# analog-out-and-pwr-amp.net
KiCad netlist of a schematic drawn in EAGLE
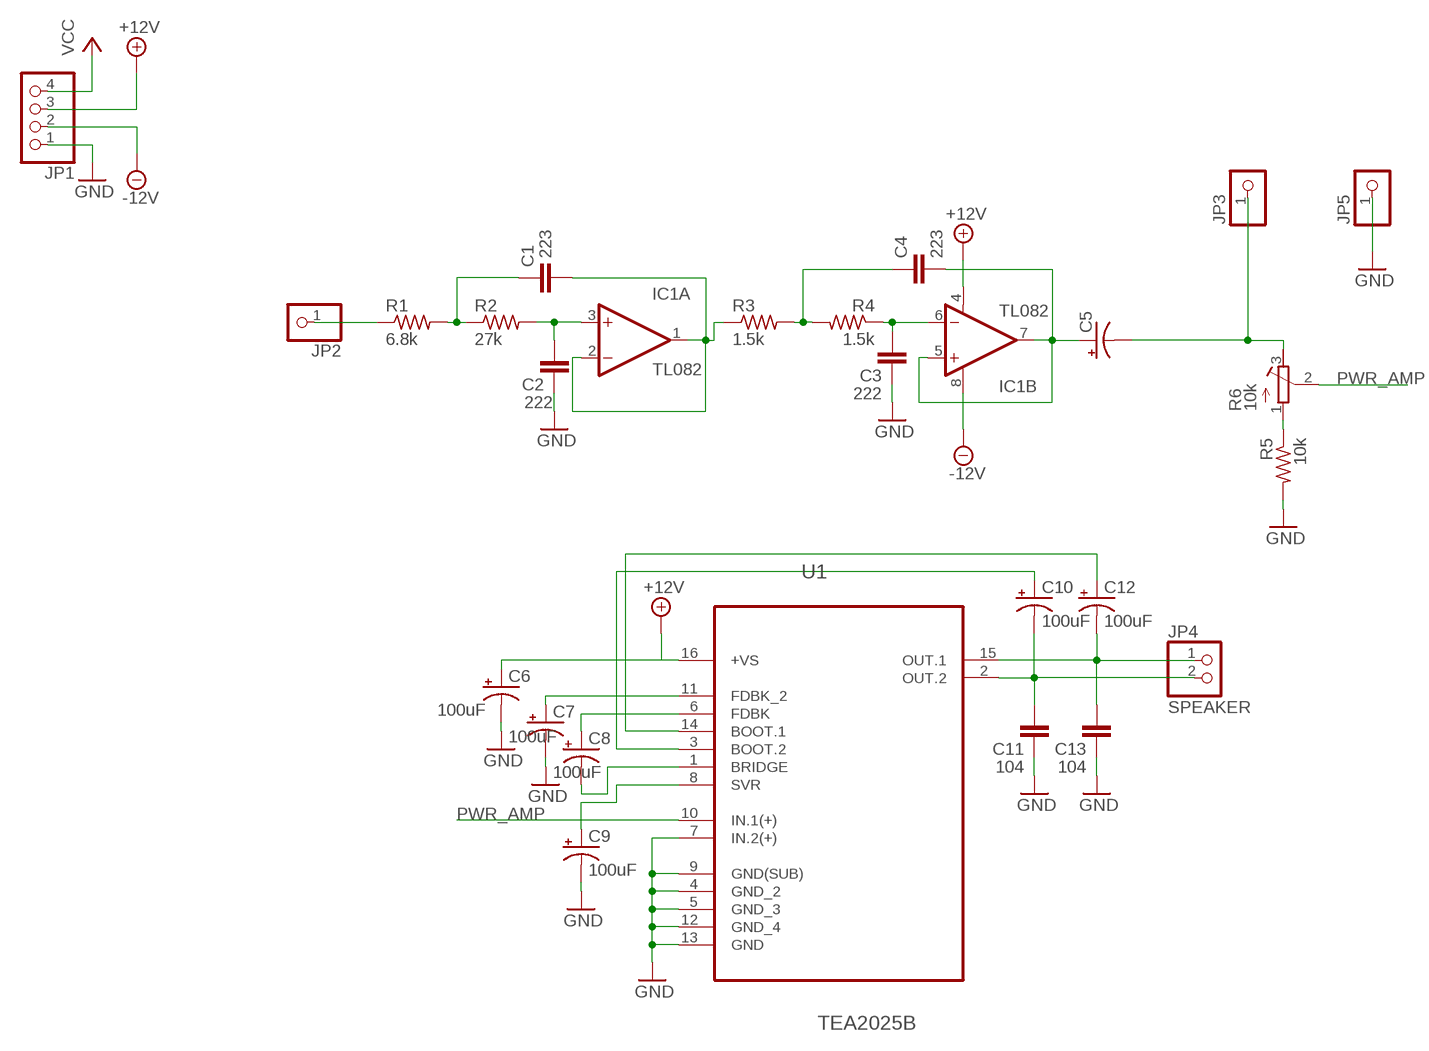
[diagram p0: schematic, sheet 1]

(export (version "E")
  (design (tool "Eeschema 10.0.6"))
  (components
    (comp (ref "C1")
      (value "223")
      (footprint "eagle-import:C025-060X050")
      (libsource (lib "eagle-import") (part "C-EUCERAMIC-CAP-COMMON"))
    )
    (comp (ref "C2")
      (value "222")
      (footprint "eagle-import:C025-060X050")
      (libsource (lib "eagle-import") (part "C-EUCERAMIC-CAP-COMMON"))
    )
    (comp (ref "C3")
      (value "222")
      (footprint "eagle-import:C025-060X050")
      (libsource (lib "eagle-import") (part "C-EUCERAMIC-CAP-COMMON"))
    )
    (comp (ref "C4")
      (value "223")
      (footprint "eagle-import:C025-060X050")
      (libsource (lib "eagle-import") (part "C-EUCERAMIC-CAP-COMMON"))
    )
    (comp (ref "C5")
      (value "CPOL-USSANYO_D")
      (footprint "eagle-import:POL-CAP-COMMON")
      (libsource (lib "eagle-import") (part "CPOL-USSANYO_D"))
    )
    (comp (ref "C6")
      (value "100uF")
      (footprint "eagle-import:POL-CAP-COMMON")
      (libsource (lib "eagle-import") (part "CPOL-USSANYO_D"))
    )
    (comp (ref "C7")
      (value "100uF")
      (footprint "eagle-import:POL-CAP-COMMON")
      (libsource (lib "eagle-import") (part "CPOL-USSANYO_D"))
    )
    (comp (ref "C8")
      (value "100uF")
      (footprint "eagle-import:POL-CAP-COMMON")
      (libsource (lib "eagle-import") (part "CPOL-USSANYO_D"))
    )
    (comp (ref "C9")
      (value "100uF")
      (footprint "eagle-import:POL-CAP-COMMON")
      (libsource (lib "eagle-import") (part "CPOL-USSANYO_D"))
    )
    (comp (ref "C10")
      (value "100uF")
      (footprint "eagle-import:POL-CAP-COMMON")
      (libsource (lib "eagle-import") (part "CPOL-USSANYO_D"))
    )
    (comp (ref "C11")
      (value "104")
      (footprint "eagle-import:C025-060X050")
      (libsource (lib "eagle-import") (part "C-EUCERAMIC-CAP-COMMON"))
    )
    (comp (ref "C12")
      (value "100uF")
      (footprint "eagle-import:POL-CAP-COMMON")
      (libsource (lib "eagle-import") (part "CPOL-USSANYO_D"))
    )
    (comp (ref "C13")
      (value "104")
      (footprint "eagle-import:C025-060X050")
      (libsource (lib "eagle-import") (part "C-EUCERAMIC-CAP-COMMON"))
    )
    (comp (ref "IC1")
      (value "TL082")
      (footprint "eagle-import:DIP08")
      (libsource (lib "eagle-import") (part "TL082"))
    )
    (comp (ref "JP1")
      (value "PINHD-1X4")
      (footprint "eagle-import:1X04")
      (libsource (lib "eagle-import") (part "PINHD-1X4"))
    )
    (comp (ref "JP2")
      (value "PINHD-1X1")
      (footprint "eagle-import:1X01")
      (libsource (lib "eagle-import") (part "PINHD-1X1"))
    )
    (comp (ref "JP3")
      (value "PINHD-1X1")
      (footprint "eagle-import:1X01")
      (libsource (lib "eagle-import") (part "PINHD-1X1"))
    )
    (comp (ref "JP4")
      (value "SPEAKER")
      (footprint "eagle-import:1X02_0.5_")
      (libsource (lib "eagle-import") (part "PINHD-1X20.5{dblquote}"))
    )
    (comp (ref "JP5")
      (value "PINHD-1X1")
      (footprint "eagle-import:1X01")
      (libsource (lib "eagle-import") (part "PINHD-1X1"))
    )
    (comp (ref "R1")
      (value "6.8k")
      (footprint "eagle-import:R-US-COMMON")
      (libsource (lib "eagle-import") (part "R-US_0207/10"))
    )
    (comp (ref "R2")
      (value "27k")
      (footprint "eagle-import:R-US-COMMON")
      (libsource (lib "eagle-import") (part "R-US_0207/10"))
    )
    (comp (ref "R3")
      (value "1.5k")
      (footprint "eagle-import:R-US-COMMON")
      (libsource (lib "eagle-import") (part "R-US_0207/10"))
    )
    (comp (ref "R4")
      (value "1.5k")
      (footprint "eagle-import:R-US-COMMON")
      (libsource (lib "eagle-import") (part "R-US_0207/10"))
    )
    (comp (ref "R5")
      (value "10k")
      (footprint "eagle-import:R-US-COMMON")
      (libsource (lib "eagle-import") (part "R-US_0207/10"))
    )
    (comp (ref "R6")
      (value "10k")
      (footprint "eagle-import:RTRIM-COMMON")
      (libsource (lib "eagle-import") (part "R-TRIMM64W"))
    )
    (comp (ref "U1")
      (value "TEA2025B")
      (footprint "eagle-import:DIP254P762X510-16")
      (libsource (lib "eagle-import") (part "TEA2025B"))
    )
  )
  (nets
    (net (code "1") (name "+12V") (class "Default")
      (node (ref "C6") (pin "+") (pinfunction "+_+") (pintype "passive"))
      (node (ref "IC1") (pin "4") (pinfunction "V-_4") (pintype "power_in"))
      (node (ref "JP1") (pin "3") (pinfunction "3_3") (pintype "passive"))
      (node (ref "U1") (pin "16") (pinfunction "+VS_16") (pintype "power_in"))
    )
    (net (code "2") (name "-12V") (class "Default")
      (node (ref "IC1") (pin "8") (pinfunction "V+_8") (pintype "power_in"))
      (node (ref "JP1") (pin "2") (pinfunction "2_2") (pintype "passive"))
    )
    (net (code "3") (name "/PWR_AMP") (class "Default")
      (node (ref "R6") (pin "2") (pinfunction "S_2") (pintype "passive"))
      (node (ref "U1") (pin "10") (pinfunction "IN.1(+)_10") (pintype "input"))
    )
    (net (code "4") (name "GND") (class "Default")
      (node (ref "C11") (pin "1") (pinfunction "1_1") (pintype "passive"))
      (node (ref "C13") (pin "1") (pinfunction "1_1") (pintype "passive"))
      (node (ref "C2") (pin "1") (pinfunction "1_1") (pintype "passive"))
      (node (ref "C3") (pin "1") (pinfunction "1_1") (pintype "passive"))
      (node (ref "C6") (pin "-") (pinfunction "-_-") (pintype "passive"))
      (node (ref "C7") (pin "-") (pinfunction "-_-") (pintype "passive"))
      (node (ref "C9") (pin "-") (pinfunction "-_-") (pintype "passive"))
      (node (ref "JP1") (pin "1") (pinfunction "1_1") (pintype "passive"))
      (node (ref "JP5") (pin "1") (pinfunction "1_1") (pintype "passive"))
      (node (ref "R5") (pin "2") (pinfunction "2_2") (pintype "passive"))
      (node (ref "U1") (pin "12") (pinfunction "GND_4_12") (pintype "passive"))
      (node (ref "U1") (pin "13") (pinfunction "GND_13") (pintype "passive"))
      (node (ref "U1") (pin "4") (pinfunction "GND_2_4") (pintype "passive"))
      (node (ref "U1") (pin "5") (pinfunction "GND_3_5") (pintype "passive"))
      (node (ref "U1") (pin "7") (pinfunction "IN.2(+)_7") (pintype "input"))
      (node (ref "U1") (pin "9") (pinfunction "GND(SUB)_9") (pintype "passive"))
    )
    (net (code "5") (name "Net-(C1-Pad1)") (class "Default")
      (node (ref "C1") (pin "1") (pinfunction "1_1") (pintype "passive"))
      (node (ref "R1") (pin "2") (pinfunction "2_2") (pintype "passive"))
      (node (ref "R2") (pin "1") (pinfunction "1_1") (pintype "passive"))
    )
    (net (code "6") (name "Net-(C4-Pad1)") (class "Default")
      (node (ref "C4") (pin "1") (pinfunction "1_1") (pintype "passive"))
      (node (ref "R3") (pin "2") (pinfunction "2_2") (pintype "passive"))
      (node (ref "R4") (pin "2") (pinfunction "2_2") (pintype "passive"))
    )
    (net (code "7") (name "Net-(IC1A-+IN)") (class "Default")
      (node (ref "C2") (pin "2") (pinfunction "2_2") (pintype "passive"))
      (node (ref "IC1") (pin "3") (pinfunction "+IN_3") (pintype "input"))
      (node (ref "R2") (pin "2") (pinfunction "2_2") (pintype "passive"))
    )
    (net (code "8") (name "Net-(IC1A--IN)") (class "Default")
      (node (ref "C1") (pin "2") (pinfunction "2_2") (pintype "passive"))
      (node (ref "IC1") (pin "1") (pinfunction "OUT_1") (pintype "output"))
      (node (ref "IC1") (pin "2") (pinfunction "-IN_2") (pintype "input"))
      (node (ref "R3") (pin "1") (pinfunction "1_1") (pintype "passive"))
    )
    (net (code "9") (name "Net-(IC1B-+IN)") (class "Default")
      (node (ref "C4") (pin "2") (pinfunction "2_2") (pintype "passive"))
      (node (ref "C5") (pin "+") (pinfunction "+_+") (pintype "passive"))
      (node (ref "IC1") (pin "5") (pinfunction "+IN_5") (pintype "input"))
      (node (ref "IC1") (pin "7") (pinfunction "OUT_7") (pintype "output"))
    )
    (net (code "10") (name "Net-(IC1B--IN)") (class "Default")
      (node (ref "C3") (pin "2") (pinfunction "2_2") (pintype "passive"))
      (node (ref "IC1") (pin "6") (pinfunction "-IN_6") (pintype "input"))
      (node (ref "R4") (pin "1") (pinfunction "1_1") (pintype "passive"))
    )
    (net (code "11") (name "Net-(JP2-Pad1)") (class "Default")
      (node (ref "JP2") (pin "1") (pinfunction "1_1") (pintype "passive"))
      (node (ref "R1") (pin "1") (pinfunction "1_1") (pintype "passive"))
    )
    (net (code "12") (name "Net-(R6-A)") (class "Default")
      (node (ref "R5") (pin "1") (pinfunction "1_1") (pintype "passive"))
      (node (ref "R6") (pin "1") (pinfunction "A_1") (pintype "passive"))
    )
    (net (code "13") (name "Net-(R6-E)") (class "Default")
      (node (ref "C5") (pin "-") (pinfunction "-_-") (pintype "passive"))
      (node (ref "JP3") (pin "1") (pinfunction "1_1") (pintype "passive"))
      (node (ref "R6") (pin "3") (pinfunction "E_3") (pintype "passive"))
    )
    (net (code "14") (name "Net-(U1-BOOT.1)") (class "Default")
      (node (ref "C12") (pin "+") (pinfunction "+_+") (pintype "passive"))
      (node (ref "U1") (pin "14") (pinfunction "BOOT.1_14") (pintype "passive"))
    )
    (net (code "15") (name "Net-(U1-BOOT.2)") (class "Default")
      (node (ref "C10") (pin "+") (pinfunction "+_+") (pintype "passive"))
      (node (ref "U1") (pin "3") (pinfunction "BOOT.2_3") (pintype "passive"))
    )
    (net (code "16") (name "Net-(U1-BRIDGE)") (class "Default")
      (node (ref "C8") (pin "-") (pinfunction "-_-") (pintype "passive"))
      (node (ref "U1") (pin "1") (pinfunction "BRIDGE_1") (pintype "passive"))
    )
    (net (code "17") (name "Net-(U1-FDBK)") (class "Default")
      (node (ref "C8") (pin "+") (pinfunction "+_+") (pintype "passive"))
      (node (ref "U1") (pin "6") (pinfunction "FDBK_6") (pintype "input"))
    )
    (net (code "18") (name "Net-(U1-FDBK_2)") (class "Default")
      (node (ref "C7") (pin "+") (pinfunction "+_+") (pintype "passive"))
      (node (ref "U1") (pin "11") (pinfunction "FDBK_2_11") (pintype "input"))
    )
    (net (code "19") (name "Net-(U1-OUT.1)") (class "Default")
      (node (ref "C12") (pin "-") (pinfunction "-_-") (pintype "passive"))
      (node (ref "C13") (pin "2") (pinfunction "2_2") (pintype "passive"))
      (node (ref "JP4") (pin "1") (pinfunction "1_1") (pintype "passive"))
      (node (ref "U1") (pin "15") (pinfunction "OUT.1_15") (pintype "output"))
    )
    (net (code "20") (name "Net-(U1-OUT.2)") (class "Default")
      (node (ref "C10") (pin "-") (pinfunction "-_-") (pintype "passive"))
      (node (ref "C11") (pin "2") (pinfunction "2_2") (pintype "passive"))
      (node (ref "JP4") (pin "2") (pinfunction "2_2") (pintype "passive"))
      (node (ref "U1") (pin "2") (pinfunction "OUT.2_2") (pintype "output"))
    )
    (net (code "21") (name "Net-(U1-SVR)") (class "Default")
      (node (ref "C9") (pin "+") (pinfunction "+_+") (pintype "passive"))
      (node (ref "U1") (pin "8") (pinfunction "SVR_8") (pintype "passive"))
    )
    (net (code "22") (name "VCC") (class "Default")
      (node (ref "JP1") (pin "4") (pinfunction "4_4") (pintype "passive"))
    )
  )
)
